# SDCARD.net
KiCad netlist of a schematic drawn in Altium Designer
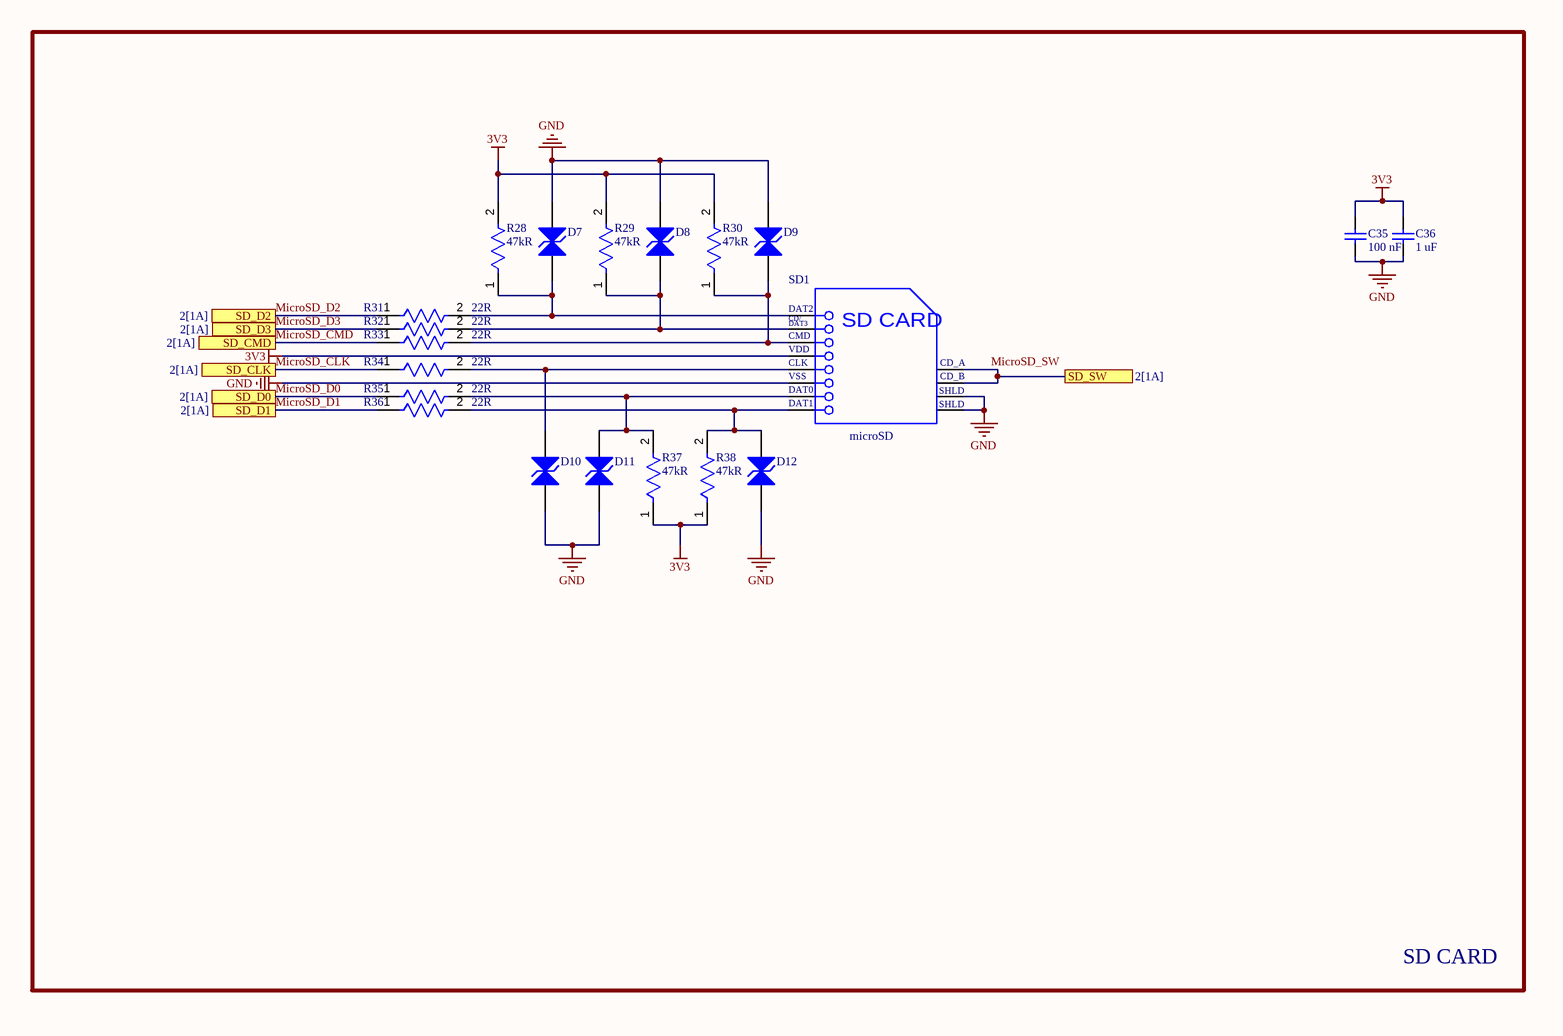
[diagram p0: SDCARD.SchDoc]

(export (version "E")
  (design (tool "Eeschema 10.0.6"))
  (components
    (comp (ref "C35")
      (value "100 nF")
      (footprint "CAPC2013X145X50LL20T25")
      (fields (field (name "MANUFACTURER") "Kemet") (field (name "PART NUMBER") "C0805C104K9RACTU"))
      (libsource (lib "Altium Content Vault") (part "CAP"))
    )
    (comp (ref "C36")
      (value "1 uF")
      (footprint "CAPC2013X135X45LL10T25")
      (fields (field (name "PART NUMBER") "GRM21BR60J225KA01K") (field (name "MANUFACTURER") "Murata"))
      (libsource (lib "Altium Content Vault") (part "CAP"))
    )
    (comp (ref "D7")
      (value "SMAJ5.0CA-E3/5A")
      (footprint "VISH-DO-214AC-2_N")
      (fields (field (name "MANUFACTURER") "Vishay Semiconductor"))
      (libsource (lib "Altium Content Vault") (part "VISH-A1A2-2"))
    )
    (comp (ref "D8")
      (value "SMAJ5.0CA-E3/5A")
      (footprint "VISH-DO-214AC-2_N")
      (fields (field (name "MANUFACTURER") "Vishay Semiconductor"))
      (libsource (lib "Altium Content Vault") (part "VISH-A1A2-2"))
    )
    (comp (ref "D9")
      (value "SMAJ5.0CA-E3/5A")
      (footprint "VISH-DO-214AC-2_N")
      (fields (field (name "MANUFACTURER") "Vishay Semiconductor"))
      (libsource (lib "Altium Content Vault") (part "VISH-A1A2-2"))
    )
    (comp (ref "D10")
      (value "SMAJ5.0CA-E3/5A")
      (footprint "VISH-DO-214AC-2_N")
      (fields (field (name "MANUFACTURER") "Vishay Semiconductor"))
      (libsource (lib "Altium Content Vault") (part "VISH-A1A2-2"))
    )
    (comp (ref "D11")
      (value "SMAJ5.0CA-E3/5A")
      (footprint "VISH-DO-214AC-2_N")
      (fields (field (name "MANUFACTURER") "Vishay Semiconductor"))
      (libsource (lib "Altium Content Vault") (part "VISH-A1A2-2"))
    )
    (comp (ref "D12")
      (value "SMAJ5.0CA-E3/5A")
      (footprint "VISH-DO-214AC-2_N")
      (fields (field (name "MANUFACTURER") "Vishay Semiconductor"))
      (libsource (lib "Altium Content Vault") (part "VISH-A1A2-2"))
    )
    (comp (ref "R28")
      (value "CRCW080547K0JNEA")
      (footprint "FP-CRCW0805-e3-MFG")
      (description "RES Thick Film, 47kΩ, 5%, 0.125W, 200ppm/°C, 0805")
      (fields (field (name "RESISTANCE") "47kR") (field (name "TOLERANCE") "5%"))
      (libsource (lib "Altium Content Vault") (part "1029c3af85768c4190bb7ad29bc67b5"))
    )
    (comp (ref "R29")
      (value "CRCW080547K0JNEA")
      (footprint "FP-CRCW0805-e3-MFG")
      (description "RES Thick Film, 47kΩ, 5%, 0.125W, 200ppm/°C, 0805")
      (fields (field (name "RESISTANCE") "47kR") (field (name "TOLERANCE") "5%"))
      (libsource (lib "Altium Content Vault") (part "1029c3af85768c4190bb7ad29bc67b5"))
    )
    (comp (ref "R30")
      (value "CRCW080547K0JNEA")
      (footprint "FP-CRCW0805-e3-MFG")
      (description "RES Thick Film, 47kΩ, 5%, 0.125W, 200ppm/°C, 0805")
      (fields (field (name "RESISTANCE") "47kR") (field (name "TOLERANCE") "5%"))
      (libsource (lib "Altium Content Vault") (part "1029c3af85768c4190bb7ad29bc67b5"))
    )
    (comp (ref "R31")
      (value "KTR10EZPF22R0")
      (footprint "FP-KTR10-IPC_C")
      (description "Res Thick Film 0805 22Ω 1% 0.125W ±100ppm/°C Automotive Paper T/R")
      (fields (field (name "RESISTANCE") "22R") (field (name "TOLERANCE") "1%"))
      (libsource (lib "Altium Content Vault") (part "1029c3af85768c4190bb7ad29bc67b5"))
    )
    (comp (ref "R32")
      (value "KTR10EZPF22R0")
      (footprint "FP-KTR10-IPC_C")
      (description "Res Thick Film 0805 22Ω 1% 0.125W ±100ppm/°C Automotive Paper T/R")
      (fields (field (name "RESISTANCE") "22R") (field (name "TOLERANCE") "1%"))
      (libsource (lib "Altium Content Vault") (part "1029c3af85768c4190bb7ad29bc67b5"))
    )
    (comp (ref "R33")
      (value "KTR10EZPF22R0")
      (footprint "FP-KTR10-IPC_C")
      (description "Res Thick Film 0805 22Ω 1% 0.125W ±100ppm/°C Automotive Paper T/R")
      (fields (field (name "RESISTANCE") "22R") (field (name "TOLERANCE") "1%"))
      (libsource (lib "Altium Content Vault") (part "1029c3af85768c4190bb7ad29bc67b5"))
    )
    (comp (ref "R34")
      (value "KTR10EZPF22R0")
      (footprint "FP-KTR10-IPC_C")
      (description "Res Thick Film 0805 22Ω 1% 0.125W ±100ppm/°C Automotive Paper T/R")
      (fields (field (name "RESISTANCE") "22R") (field (name "TOLERANCE") "1%"))
      (libsource (lib "Altium Content Vault") (part "1029c3af85768c4190bb7ad29bc67b5"))
    )
    (comp (ref "R35")
      (value "KTR10EZPF22R0")
      (footprint "FP-KTR10-IPC_C")
      (description "Res Thick Film 0805 22Ω 1% 0.125W ±100ppm/°C Automotive Paper T/R")
      (fields (field (name "RESISTANCE") "22R") (field (name "TOLERANCE") "1%"))
      (libsource (lib "Altium Content Vault") (part "1029c3af85768c4190bb7ad29bc67b5"))
    )
    (comp (ref "R36")
      (value "KTR10EZPF22R0")
      (footprint "FP-KTR10-IPC_C")
      (description "Res Thick Film 0805 22Ω 1% 0.125W ±100ppm/°C Automotive Paper T/R")
      (fields (field (name "RESISTANCE") "22R") (field (name "TOLERANCE") "1%"))
      (libsource (lib "Altium Content Vault") (part "1029c3af85768c4190bb7ad29bc67b5"))
    )
    (comp (ref "R37")
      (value "CRCW080547K0JNEA")
      (footprint "FP-CRCW0805-e3-MFG")
      (description "RES Thick Film, 47kΩ, 5%, 0.125W, 200ppm/°C, 0805")
      (fields (field (name "RESISTANCE") "47kR") (field (name "TOLERANCE") "5%"))
      (libsource (lib "Altium Content Vault") (part "1029c3af85768c4190bb7ad29bc67b5"))
    )
    (comp (ref "R38")
      (value "CRCW080547K0JNEA")
      (footprint "FP-CRCW0805-e3-MFG")
      (description "RES Thick Film, 47kΩ, 5%, 0.125W, 200ppm/°C, 0805")
      (fields (field (name "RESISTANCE") "47kR") (field (name "TOLERANCE") "5%"))
      (libsource (lib "Altium Content Vault") (part "1029c3af85768c4190bb7ad29bc67b5"))
    )
    (comp (ref "SD1")
      (value "104031-0811")
      (footprint "MOLX-104031-0811_V")
      (description "Micro SD Card, RA, -25 to 85 degC, 8-Pin SMD, RoHS, Tape and Reel")
      (fields (field (name "CARD TYPE") "microSD") (field (name "MANUFACTURER") "Molex"))
      (libsource (lib "Altium Content Vault") (part "CN-SD-8-2SW-2S"))
    )
  )
  (nets
    (net (code "1") (name "/MicroSD_CLK") (class "Default")
      (node (ref "R34") (pin "1") (pinfunction "1_1") (pintype "passive"))
    )
    (net (code "2") (name "/MicroSD_CMD") (class "Default")
      (node (ref "R33") (pin "1") (pinfunction "1_1") (pintype "passive"))
    )
    (net (code "3") (name "/MicroSD_D0") (class "Default")
      (node (ref "R35") (pin "1") (pinfunction "1_1") (pintype "passive"))
    )
    (net (code "4") (name "/MicroSD_D1") (class "Default")
      (node (ref "R36") (pin "1") (pinfunction "1_1") (pintype "passive"))
    )
    (net (code "5") (name "/MicroSD_D2") (class "Default")
      (node (ref "R31") (pin "1") (pinfunction "1_1") (pintype "passive"))
    )
    (net (code "6") (name "/MicroSD_D3") (class "Default")
      (node (ref "R32") (pin "1") (pinfunction "1_1") (pintype "passive"))
    )
    (net (code "7") (name "/MicroSD_SW") (class "Default")
      (node (ref "SD1") (pin "10") (pinfunction "CD_B_10") (pintype "passive"))
      (node (ref "SD1") (pin "9") (pinfunction "CD_A_9") (pintype "passive"))
    )
    (net (code "8") (name "3V3") (class "Default")
      (node (ref "C35") (pin "2") (pinfunction "2_2") (pintype "passive"))
      (node (ref "C36") (pin "2") (pinfunction "2_2") (pintype "passive"))
      (node (ref "R28") (pin "2") (pinfunction "2_2") (pintype "passive"))
      (node (ref "R29") (pin "2") (pinfunction "2_2") (pintype "passive"))
      (node (ref "R30") (pin "2") (pinfunction "2_2") (pintype "passive"))
      (node (ref "R37") (pin "1") (pinfunction "1_1") (pintype "passive"))
      (node (ref "R38") (pin "1") (pinfunction "1_1") (pintype "passive"))
      (node (ref "SD1") (pin "4") (pinfunction "VDD_4") (pintype "passive"))
    )
    (net (code "9") (name "GND") (class "Default")
      (node (ref "C35") (pin "1") (pinfunction "1_1") (pintype "passive"))
      (node (ref "C36") (pin "1") (pinfunction "1_1") (pintype "passive"))
      (node (ref "D10") (pin "2") (pinfunction "A2_2") (pintype "passive"))
      (node (ref "D11") (pin "2") (pinfunction "A2_2") (pintype "passive"))
      (node (ref "D12") (pin "2") (pinfunction "A2_2") (pintype "passive"))
      (node (ref "D7") (pin "1") (pinfunction "A1_1") (pintype "passive"))
      (node (ref "D8") (pin "1") (pinfunction "A1_1") (pintype "passive"))
      (node (ref "D9") (pin "1") (pinfunction "A1_1") (pintype "passive"))
      (node (ref "SD1") (pin "11") (pinfunction "SHLD1_11") (pintype "passive"))
      (node (ref "SD1") (pin "12") (pinfunction "SHLD2_12") (pintype "passive"))
      (node (ref "SD1") (pin "6") (pinfunction "VSS2_6") (pintype "passive"))
    )
    (net (code "10") (name "Net-(D7-A2)") (class "Default")
      (node (ref "D7") (pin "2") (pinfunction "A2_2") (pintype "passive"))
      (node (ref "R28") (pin "1") (pinfunction "1_1") (pintype "passive"))
      (node (ref "R31") (pin "2") (pinfunction "2_2") (pintype "passive"))
      (node (ref "SD1") (pin "1") (pinfunction "CD/DAT3_1") (pintype "passive"))
    )
    (net (code "11") (name "Net-(D8-A2)") (class "Default")
      (node (ref "D8") (pin "2") (pinfunction "A2_2") (pintype "passive"))
      (node (ref "R29") (pin "1") (pinfunction "1_1") (pintype "passive"))
      (node (ref "R32") (pin "2") (pinfunction "2_2") (pintype "passive"))
      (node (ref "SD1") (pin "2") (pinfunction "CMD_2") (pintype "passive"))
    )
    (net (code "12") (name "Net-(D9-A2)") (class "Default")
      (node (ref "D9") (pin "2") (pinfunction "A2_2") (pintype "passive"))
      (node (ref "R30") (pin "1") (pinfunction "1_1") (pintype "passive"))
      (node (ref "R33") (pin "2") (pinfunction "2_2") (pintype "passive"))
      (node (ref "SD1") (pin "3") (pinfunction "VSS1_3") (pintype "passive"))
    )
    (net (code "13") (name "Net-(D10-A1)") (class "Default")
      (node (ref "D10") (pin "1") (pinfunction "A1_1") (pintype "passive"))
      (node (ref "R34") (pin "2") (pinfunction "2_2") (pintype "passive"))
      (node (ref "SD1") (pin "5") (pinfunction "CLK_5") (pintype "passive"))
    )
    (net (code "14") (name "Net-(D11-A1)") (class "Default")
      (node (ref "D11") (pin "1") (pinfunction "A1_1") (pintype "passive"))
      (node (ref "R35") (pin "2") (pinfunction "2_2") (pintype "passive"))
      (node (ref "R37") (pin "2") (pinfunction "2_2") (pintype "passive"))
      (node (ref "SD1") (pin "7") (pinfunction "DAT0_7") (pintype "passive"))
    )
    (net (code "15") (name "Net-(D12-A1)") (class "Default")
      (node (ref "D12") (pin "1") (pinfunction "A1_1") (pintype "passive"))
      (node (ref "R36") (pin "2") (pinfunction "2_2") (pintype "passive"))
      (node (ref "R38") (pin "2") (pinfunction "2_2") (pintype "passive"))
      (node (ref "SD1") (pin "8") (pinfunction "DAT1_8") (pintype "passive"))
    )
  )
)
